# Laikata.net
KiCad netlist of a schematic drawn in EAGLE
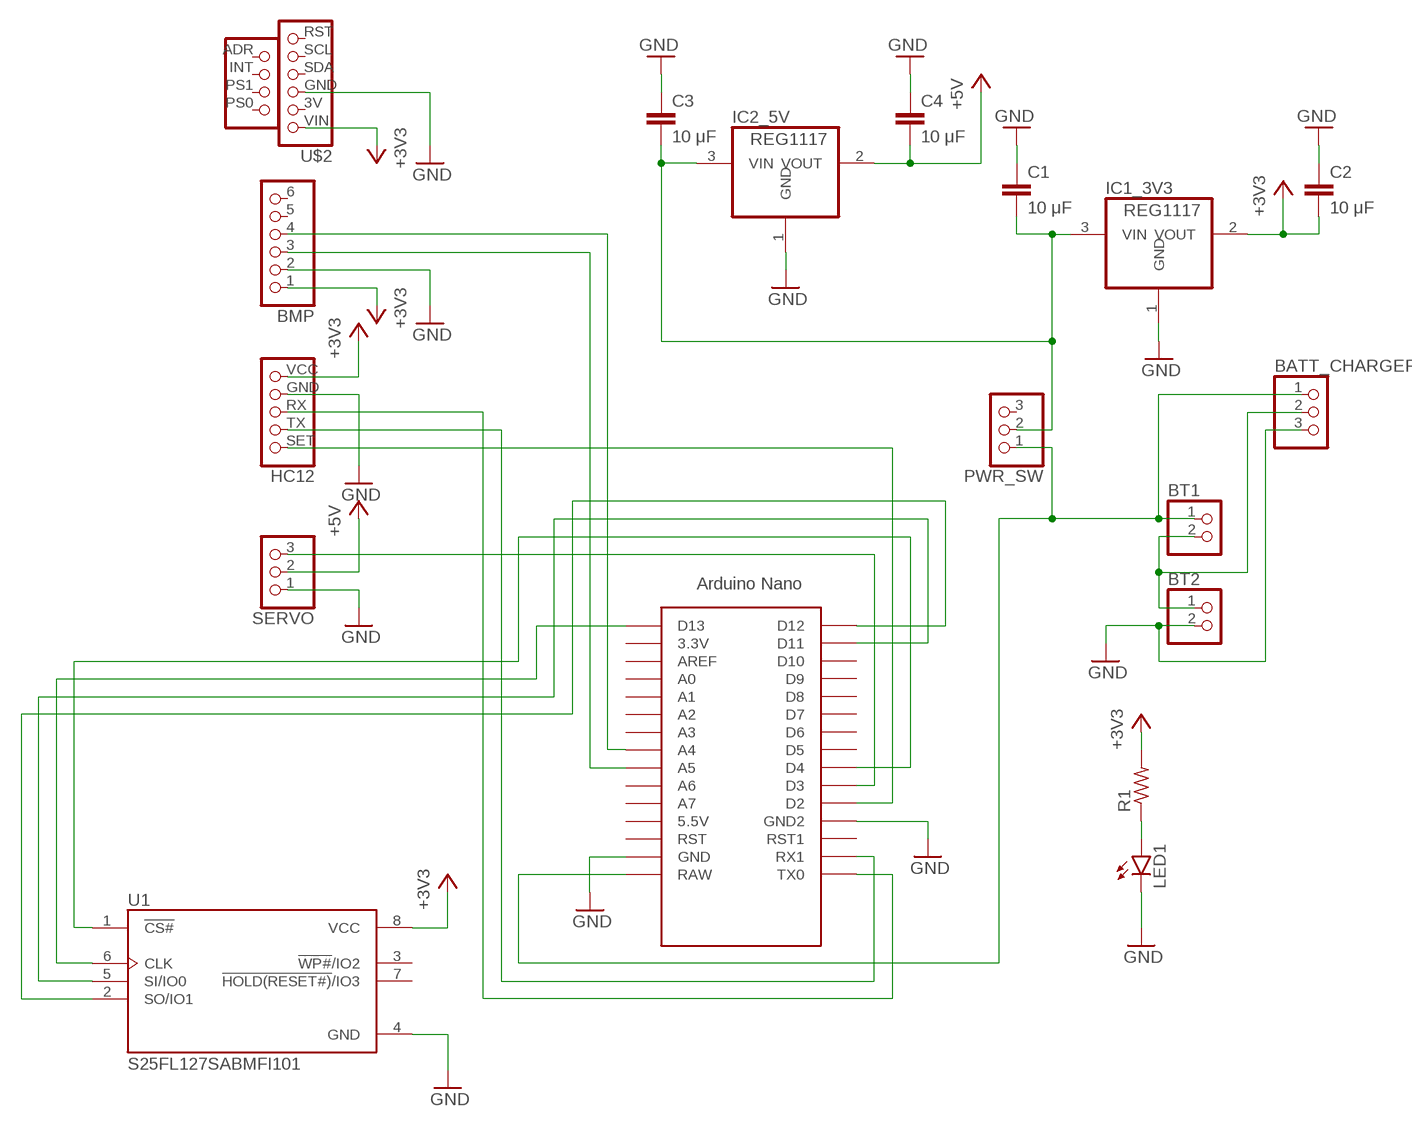
[diagram p0: schematic, sheet 1]

(export (version "E")
  (design (tool "Eeschema 10.0.6"))
  (components
    (comp (ref "BATT_CHARGER")
      (value "PINHD-1X3")
      (footprint "eagle-import:1X03")
      (libsource (lib "eagle-import") (part "PINHD-1X3"))
    )
    (comp (ref "BMP")
      (value "PINHD-1X6")
      (footprint "eagle-import:1X06")
      (libsource (lib "eagle-import") (part "PINHD-1X6"))
    )
    (comp (ref "BT1")
      (value "PINHD-1X2")
      (footprint "eagle-import:1X02")
      (libsource (lib "eagle-import") (part "PINHD-1X2"))
    )
    (comp (ref "BT2")
      (value "PINHD-1X2")
      (footprint "eagle-import:1X02")
      (libsource (lib "eagle-import") (part "PINHD-1X2"))
    )
    (comp (ref "C1")
      (value "10 μF")
      (footprint "eagle-import:C1210")
      (libsource (lib "eagle-import") (part "C-EUC1210"))
    )
    (comp (ref "C2")
      (value "10 μF")
      (footprint "eagle-import:C1210")
      (libsource (lib "eagle-import") (part "C-EUC1210"))
    )
    (comp (ref "C3")
      (value "10 μF")
      (footprint "eagle-import:C1210")
      (libsource (lib "eagle-import") (part "C-EUC1210"))
    )
    (comp (ref "C4")
      (value "10 μF")
      (footprint "eagle-import:C1210")
      (libsource (lib "eagle-import") (part "C-EUC1210"))
    )
    (comp (ref "HC12")
      (value "HC12")
      (footprint "eagle-import:HC12")
      (libsource (lib "eagle-import") (part "HC12"))
    )
    (comp (ref "IC1_3V3")
      (value "REG1117")
      (footprint "eagle-import:SOT223")
      (libsource (lib "eagle-import") (part "REG1117"))
    )
    (comp (ref "IC2_5V")
      (value "REG1117")
      (footprint "eagle-import:SOT223")
      (libsource (lib "eagle-import") (part "REG1117"))
    )
    (comp (ref "LED1")
      (value "LED3MM")
      (footprint "eagle-import:LED3MM")
      (libsource (lib "eagle-import") (part "LED3MM"))
    )
    (comp (ref "PWR_SW")
      (value "PINHD-1X3")
      (footprint "eagle-import:1X03")
      (libsource (lib "eagle-import") (part "PINHD-1X3"))
    )
    (comp (ref "R1")
      (value "R-US_R1206")
      (footprint "eagle-import:R1206")
      (libsource (lib "eagle-import") (part "R-US_R1206"))
    )
    (comp (ref "SERVO")
      (value "PINHD-1X3")
      (footprint "eagle-import:1X03")
      (libsource (lib "eagle-import") (part "PINHD-1X3"))
    )
    (comp (ref "U$1")
      (value "NANO")
      (footprint "eagle-import:NANO")
      (libsource (lib "eagle-import") (part "NANO"))
    )
    (comp (ref "U$2")
      (value "IMU")
      (footprint "eagle-import:IMU")
      (libsource (lib "eagle-import") (part "IMU"))
    )
    (comp (ref "U1")
      (value "S25FL127SABMFI101")
      (footprint "eagle-import:SOIC127P800X216-8N")
      (fields (field (name "MF") "Cypress Semiconductor"))
      (libsource (lib "eagle-import") (part "S25FL127SABMFI101"))
    )
  )
  (nets
    (net (code "1") (name "+3V3") (class "Default")
      (node (ref "BMP") (pin "1") (pinfunction "1_1") (pintype "passive"))
      (node (ref "C2") (pin "2") (pinfunction "2_2") (pintype "passive"))
      (node (ref "HC12") (pin "VCC") (pinfunction "VCC_VCC") (pintype "passive"))
      (node (ref "IC1_3V3") (pin "2") (pinfunction "VOUT_2") (pintype "output"))
      (node (ref "R1") (pin "2") (pinfunction "2_2") (pintype "passive"))
      (node (ref "U$2") (pin "VIN") (pinfunction "VIN_VIN") (pintype "passive"))
      (node (ref "U1") (pin "8") (pinfunction "VCC_8") (pintype "power_in"))
    )
    (net (code "2") (name "+5V") (class "Default")
      (node (ref "C4") (pin "2") (pinfunction "2_2") (pintype "passive"))
      (node (ref "IC2_5V") (pin "2") (pinfunction "VOUT_2") (pintype "output"))
      (node (ref "SERVO") (pin "2") (pinfunction "2_2") (pintype "passive"))
    )
    (net (code "3") (name "GND") (class "Default")
      (node (ref "BATT_CHARGER") (pin "3") (pinfunction "3_3") (pintype "passive"))
      (node (ref "BMP") (pin "2") (pinfunction "2_2") (pintype "passive"))
      (node (ref "BT2") (pin "2") (pinfunction "2_2") (pintype "passive"))
      (node (ref "C1") (pin "1") (pinfunction "1_1") (pintype "passive"))
      (node (ref "C2") (pin "1") (pinfunction "1_1") (pintype "passive"))
      (node (ref "C3") (pin "1") (pinfunction "1_1") (pintype "passive"))
      (node (ref "C4") (pin "1") (pinfunction "1_1") (pintype "passive"))
      (node (ref "HC12") (pin "GND") (pinfunction "GND_GND") (pintype "passive"))
      (node (ref "IC1_3V3") (pin "1") (pinfunction "GND_1") (pintype "power_in"))
      (node (ref "IC2_5V") (pin "1") (pinfunction "GND_1") (pintype "power_in"))
      (node (ref "LED1") (pin "K") (pinfunction "C_K") (pintype "passive"))
      (node (ref "SERVO") (pin "1") (pinfunction "1_1") (pintype "passive"))
      (node (ref "U$1") (pin "GND") (pinfunction "GND_GND") (pintype "bidirectional"))
      (node (ref "U$1") (pin "GND1") (pinfunction "GND2_GND1") (pintype "bidirectional"))
      (node (ref "U$2") (pin "GND") (pinfunction "GND_GND") (pintype "passive"))
      (node (ref "U1") (pin "4") (pinfunction "GND_4") (pintype "power_in"))
    )
    (net (code "4") (name "Net-(BATT_CHARGER-Pad1)") (class "Default")
      (node (ref "BATT_CHARGER") (pin "1") (pinfunction "1_1") (pintype "passive"))
      (node (ref "BT1") (pin "1") (pinfunction "1_1") (pintype "passive"))
      (node (ref "PWR_SW") (pin "1") (pinfunction "1_1") (pintype "passive"))
      (node (ref "U$1") (pin "RAW") (pinfunction "RAW_RAW") (pintype "bidirectional"))
    )
    (net (code "5") (name "Net-(BATT_CHARGER-Pad2)") (class "Default")
      (node (ref "BATT_CHARGER") (pin "2") (pinfunction "2_2") (pintype "passive"))
      (node (ref "BT1") (pin "2") (pinfunction "2_2") (pintype "passive"))
      (node (ref "BT2") (pin "1") (pinfunction "1_1") (pintype "passive"))
    )
    (net (code "6") (name "Net-(BMP-Pad3)") (class "Default")
      (node (ref "BMP") (pin "3") (pinfunction "3_3") (pintype "passive"))
      (node (ref "U$1") (pin "A5") (pinfunction "A5_A5") (pintype "bidirectional"))
    )
    (net (code "7") (name "Net-(BMP-Pad4)") (class "Default")
      (node (ref "BMP") (pin "4") (pinfunction "4_4") (pintype "passive"))
      (node (ref "U$1") (pin "A4") (pinfunction "A4_A4") (pintype "bidirectional"))
    )
    (net (code "8") (name "Net-(HC12-PadRX)") (class "Default")
      (node (ref "HC12") (pin "RX") (pinfunction "RX_RX") (pintype "passive"))
      (node (ref "U$1") (pin "TX0") (pinfunction "TX0_TX0") (pintype "bidirectional"))
    )
    (net (code "9") (name "Net-(HC12-PadSET)") (class "Default")
      (node (ref "HC12") (pin "SET") (pinfunction "SET_SET") (pintype "passive"))
      (node (ref "U$1") (pin "D2") (pinfunction "D2_D2") (pintype "bidirectional"))
    )
    (net (code "10") (name "Net-(HC12-PadTX)") (class "Default")
      (node (ref "HC12") (pin "TX") (pinfunction "TX_TX") (pintype "passive"))
      (node (ref "U$1") (pin "RX1") (pinfunction "RX1_RX1") (pintype "bidirectional"))
    )
    (net (code "11") (name "Net-(IC1_3V3-VIN)") (class "Default")
      (node (ref "C1") (pin "2") (pinfunction "2_2") (pintype "passive"))
      (node (ref "C3") (pin "2") (pinfunction "2_2") (pintype "passive"))
      (node (ref "IC1_3V3") (pin "3") (pinfunction "VIN_3") (pintype "input"))
      (node (ref "IC2_5V") (pin "3") (pinfunction "VIN_3") (pintype "input"))
      (node (ref "PWR_SW") (pin "2") (pinfunction "2_2") (pintype "passive"))
    )
    (net (code "12") (name "Net-(LED1-PadA)") (class "Default")
      (node (ref "LED1") (pin "A") (pinfunction "A_A") (pintype "passive"))
      (node (ref "R1") (pin "1") (pinfunction "1_1") (pintype "passive"))
    )
    (net (code "13") (name "Net-(SERVO-Pad3)") (class "Default")
      (node (ref "SERVO") (pin "3") (pinfunction "3_3") (pintype "passive"))
      (node (ref "U$1") (pin "D3") (pinfunction "D3_D3") (pintype "bidirectional"))
    )
    (net (code "14") (name "Net-(U1-CLK)") (class "Default")
      (node (ref "U$1") (pin "D13") (pinfunction "D13_D13") (pintype "bidirectional"))
      (node (ref "U1") (pin "6") (pinfunction "CLK_6") (pintype "input"))
    )
    (net (code "15") (name "Net-(U1-SI{slash}IO0)") (class "Default")
      (node (ref "U$1") (pin "D11") (pinfunction "D11_D11") (pintype "bidirectional"))
      (node (ref "U1") (pin "5") (pinfunction "SI/IO0_5") (pintype "bidirectional"))
    )
    (net (code "16") (name "Net-(U1-SO{slash}IO1)") (class "Default")
      (node (ref "U$1") (pin "D12") (pinfunction "D12_D12") (pintype "bidirectional"))
      (node (ref "U1") (pin "2") (pinfunction "SO/IO1_2") (pintype "bidirectional"))
    )
    (net (code "17") (name "Net-(U1-~{CS#})") (class "Default")
      (node (ref "U$1") (pin "D4") (pinfunction "D4_D4") (pintype "bidirectional"))
      (node (ref "U1") (pin "1") (pinfunction "~{CS#}_1") (pintype "input"))
    )
    (net (code "18") (name "unconnected-(BMP-Pad5)") (class "Default")
      (node (ref "BMP") (pin "5") (pinfunction "5_5") (pintype "passive"))
    )
    (net (code "19") (name "unconnected-(BMP-Pad6)") (class "Default")
      (node (ref "BMP") (pin "6") (pinfunction "6_6") (pintype "passive"))
    )
    (net (code "20") (name "unconnected-(PWR_SW-Pad3)") (class "Default")
      (node (ref "PWR_SW") (pin "3") (pinfunction "3_3") (pintype "passive"))
    )
    (net (code "21") (name "unconnected-(U$1-5.5V-Pad5V)") (class "Default")
      (node (ref "U$1") (pin "5V") (pinfunction "5.5V_5V") (pintype "bidirectional"))
    )
    (net (code "22") (name "unconnected-(U$1-Pad3.3V)") (class "Default")
      (node (ref "U$1") (pin "3.3V") (pinfunction "3.3V_3.3V") (pintype "bidirectional"))
    )
    (net (code "23") (name "unconnected-(U$1-PadA0)") (class "Default")
      (node (ref "U$1") (pin "A0") (pinfunction "A0_A0") (pintype "bidirectional"))
    )
    (net (code "24") (name "unconnected-(U$1-PadA1)") (class "Default")
      (node (ref "U$1") (pin "A1") (pinfunction "A1_A1") (pintype "bidirectional"))
    )
    (net (code "25") (name "unconnected-(U$1-PadA2)") (class "Default")
      (node (ref "U$1") (pin "A2") (pinfunction "A2_A2") (pintype "bidirectional"))
    )
    (net (code "26") (name "unconnected-(U$1-PadA3)") (class "Default")
      (node (ref "U$1") (pin "A3") (pinfunction "A3_A3") (pintype "bidirectional"))
    )
    (net (code "27") (name "unconnected-(U$1-PadA6)") (class "Default")
      (node (ref "U$1") (pin "A6") (pinfunction "A6_A6") (pintype "bidirectional"))
    )
    (net (code "28") (name "unconnected-(U$1-PadA7)") (class "Default")
      (node (ref "U$1") (pin "A7") (pinfunction "A7_A7") (pintype "bidirectional"))
    )
    (net (code "29") (name "unconnected-(U$1-PadAREF)") (class "Default")
      (node (ref "U$1") (pin "AREF") (pinfunction "AREF_AREF") (pintype "bidirectional"))
    )
    (net (code "30") (name "unconnected-(U$1-PadD5)") (class "Default")
      (node (ref "U$1") (pin "D5") (pinfunction "D5_D5") (pintype "bidirectional"))
    )
    (net (code "31") (name "unconnected-(U$1-PadD6)") (class "Default")
      (node (ref "U$1") (pin "D6") (pinfunction "D6_D6") (pintype "bidirectional"))
    )
    (net (code "32") (name "unconnected-(U$1-PadD7)") (class "Default")
      (node (ref "U$1") (pin "D7") (pinfunction "D7_D7") (pintype "bidirectional"))
    )
    (net (code "33") (name "unconnected-(U$1-PadD8)") (class "Default")
      (node (ref "U$1") (pin "D8") (pinfunction "D8_D8") (pintype "bidirectional"))
    )
    (net (code "34") (name "unconnected-(U$1-PadD9)") (class "Default")
      (node (ref "U$1") (pin "D9") (pinfunction "D9_D9") (pintype "bidirectional"))
    )
    (net (code "35") (name "unconnected-(U$1-PadD10)") (class "Default")
      (node (ref "U$1") (pin "D10") (pinfunction "D10_D10") (pintype "bidirectional"))
    )
    (net (code "36") (name "unconnected-(U$1-PadRST)") (class "Default")
      (node (ref "U$1") (pin "RST") (pinfunction "RST_RST") (pintype "bidirectional"))
    )
    (net (code "37") (name "unconnected-(U$1-PadRST1)") (class "Default")
      (node (ref "U$1") (pin "RST1") (pinfunction "RST1_RST1") (pintype "bidirectional"))
    )
    (net (code "38") (name "unconnected-(U$2-Pad3V)") (class "Default")
      (node (ref "U$2") (pin "3V") (pinfunction "3V_3V") (pintype "passive"))
    )
    (net (code "39") (name "unconnected-(U$2-PadADR)") (class "Default")
      (node (ref "U$2") (pin "ADR") (pinfunction "ADR_ADR") (pintype "passive"))
    )
    (net (code "40") (name "unconnected-(U$2-PadINT)") (class "Default")
      (node (ref "U$2") (pin "INT") (pinfunction "INT_INT") (pintype "passive"))
    )
    (net (code "41") (name "unconnected-(U$2-PadPS0)") (class "Default")
      (node (ref "U$2") (pin "PS0") (pinfunction "PS0_PS0") (pintype "passive"))
    )
    (net (code "42") (name "unconnected-(U$2-PadPS1)") (class "Default")
      (node (ref "U$2") (pin "PS1") (pinfunction "PS1_PS1") (pintype "passive"))
    )
    (net (code "43") (name "unconnected-(U$2-PadRST)") (class "Default")
      (node (ref "U$2") (pin "RST") (pinfunction "RST_RST") (pintype "passive"))
    )
    (net (code "44") (name "unconnected-(U$2-PadSCL)") (class "Default")
      (node (ref "U$2") (pin "SCL") (pinfunction "SCL_SCL") (pintype "passive"))
    )
    (net (code "45") (name "unconnected-(U$2-PadSDA)") (class "Default")
      (node (ref "U$2") (pin "SDA") (pinfunction "SDA_SDA") (pintype "passive"))
    )
    (net (code "46") (name "unconnected-(U1-~{HOLD(RESET#})~{{slash}IO3}-Pad7)") (class "Default")
      (node (ref "U1") (pin "7") (pinfunction "~{HOLD(RESET#})~{/IO3}_7") (pintype "bidirectional"))
    )
    (net (code "47") (name "unconnected-(U1-~{WP#}{slash}IO2-Pad3)") (class "Default")
      (node (ref "U1") (pin "3") (pinfunction "~{WP#}/IO2_3") (pintype "bidirectional"))
    )
  )
)
